# breakout.net
KiCad netlist of a schematic drawn in EAGLE
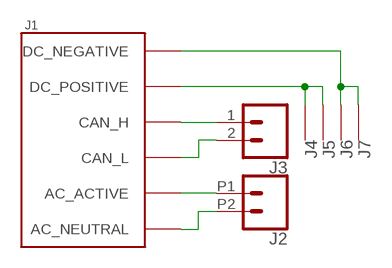
[diagram p0: schematic, sheet 1]

(export (version "E")
  (design (tool "Eeschema 10.0.6"))
  (components
    (comp (ref "J1")
      (value "FLATPACK2_CON")
      (footprint "eagle-import:FLATPACK2_CON")
      (libsource (lib "eagle-import") (part "FLATPACK2_CON"))
    )
    (comp (ref "J2")
      (value "WEIDMULLER_PM_508")
      (footprint "eagle-import:WEIDMULLER_PM_508")
      (libsource (lib "eagle-import") (part "WEIDMULLER_PM_508"))
    )
    (comp (ref "J3")
      (value "CONN_02POGO_PIN_HOLES_ONLY")
      (footprint "eagle-import:1X02_PP_HOLES_ONLY")
      (libsource (lib "eagle-import") (part "CONN_02POGO_PIN_HOLES_ONLY"))
    )
    (comp (ref "J4")
      (value "FLATPACK2_DC_LUG")
      (footprint "eagle-import:FLATPACK2_DC_LUG")
      (libsource (lib "eagle-import") (part "FLATPACK2_DC_LUG"))
    )
    (comp (ref "J5")
      (value "FLATPACK2_DC_LUG")
      (footprint "eagle-import:FLATPACK2_DC_LUG")
      (libsource (lib "eagle-import") (part "FLATPACK2_DC_LUG"))
    )
    (comp (ref "J6")
      (value "FLATPACK2_DC_LUG")
      (footprint "eagle-import:FLATPACK2_DC_LUG")
      (libsource (lib "eagle-import") (part "FLATPACK2_DC_LUG"))
    )
    (comp (ref "J7")
      (value "FLATPACK2_DC_LUG")
      (footprint "eagle-import:FLATPACK2_DC_LUG")
      (libsource (lib "eagle-import") (part "FLATPACK2_DC_LUG"))
    )
  )
  (nets
    (net (code "1") (name "Net-(J1-CAN_H)") (class "Default")
      (node (ref "J1") (pin "CAN_H_TOP") (pinfunction "CAN_H_CAN_H_TOP") (pintype "bidirectional"))
      (node (ref "J3") (pin "1") (pinfunction "1_1") (pintype "passive"))
    )
    (net (code "2") (name "Net-(J1-CAN_L)") (class "Default")
      (node (ref "J1") (pin "CAN_L_TOP") (pinfunction "CAN_L_CAN_L_TOP") (pintype "bidirectional"))
      (node (ref "J3") (pin "2") (pinfunction "2_2") (pintype "passive"))
    )
    (net (code "3") (name "Net-(J2-1)") (class "Default")
      (node (ref "J1") (pin "AC_ACTIVE_BOTTOM") (pinfunction "AC_ACTIVE_AC_ACTIVE_BOTTOM") (pintype "input"))
      (node (ref "J1") (pin "AC_ACTIVE_TOP") (pinfunction "AC_ACTIVE_AC_ACTIVE_TOP") (pintype "input"))
      (node (ref "J2") (pin "P1") (pinfunction "1_P1") (pintype "passive"))
    )
    (net (code "4") (name "Net-(J2-2)") (class "Default")
      (node (ref "J1") (pin "AC_NEUTRAL_BOTTOM") (pinfunction "AC_NEUTRAL_AC_NEUTRAL_BOTTOM") (pintype "input"))
      (node (ref "J1") (pin "AC_NEUTRAL_TOP") (pinfunction "AC_NEUTRAL_AC_NEUTRAL_TOP") (pintype "input"))
      (node (ref "J2") (pin "P2") (pinfunction "2_P2") (pintype "passive"))
    )
    (net (code "5") (name "Net-(J4-PIN)") (class "Default")
      (node (ref "J1") (pin "DC_POSITIVE_BOTTOM") (pinfunction "DC_POSITIVE_DC_POSITIVE_BOTTOM") (pintype "output"))
      (node (ref "J1") (pin "DC_POSITIVE_TOP") (pinfunction "DC_POSITIVE_DC_POSITIVE_TOP") (pintype "output"))
      (node (ref "J4") (pin "P$1") (pinfunction "PIN_P$1") (pintype "passive"))
      (node (ref "J5") (pin "P$1") (pinfunction "PIN_P$1") (pintype "passive"))
    )
    (net (code "6") (name "Net-(J6-PIN)") (class "Default")
      (node (ref "J1") (pin "DC_NEGATIVE_BOTTOM") (pinfunction "DC_NEGATIVE_DC_NEGATIVE_BOTTOM") (pintype "output"))
      (node (ref "J1") (pin "DC_NEGATIVE_TOP") (pinfunction "DC_NEGATIVE_DC_NEGATIVE_TOP") (pintype "output"))
      (node (ref "J6") (pin "P$1") (pinfunction "PIN_P$1") (pintype "passive"))
      (node (ref "J7") (pin "P$1") (pinfunction "PIN_P$1") (pintype "passive"))
    )
  )
)
